# SLIM-PLO.net
KiCad netlist of a schematic drawn in EAGLE
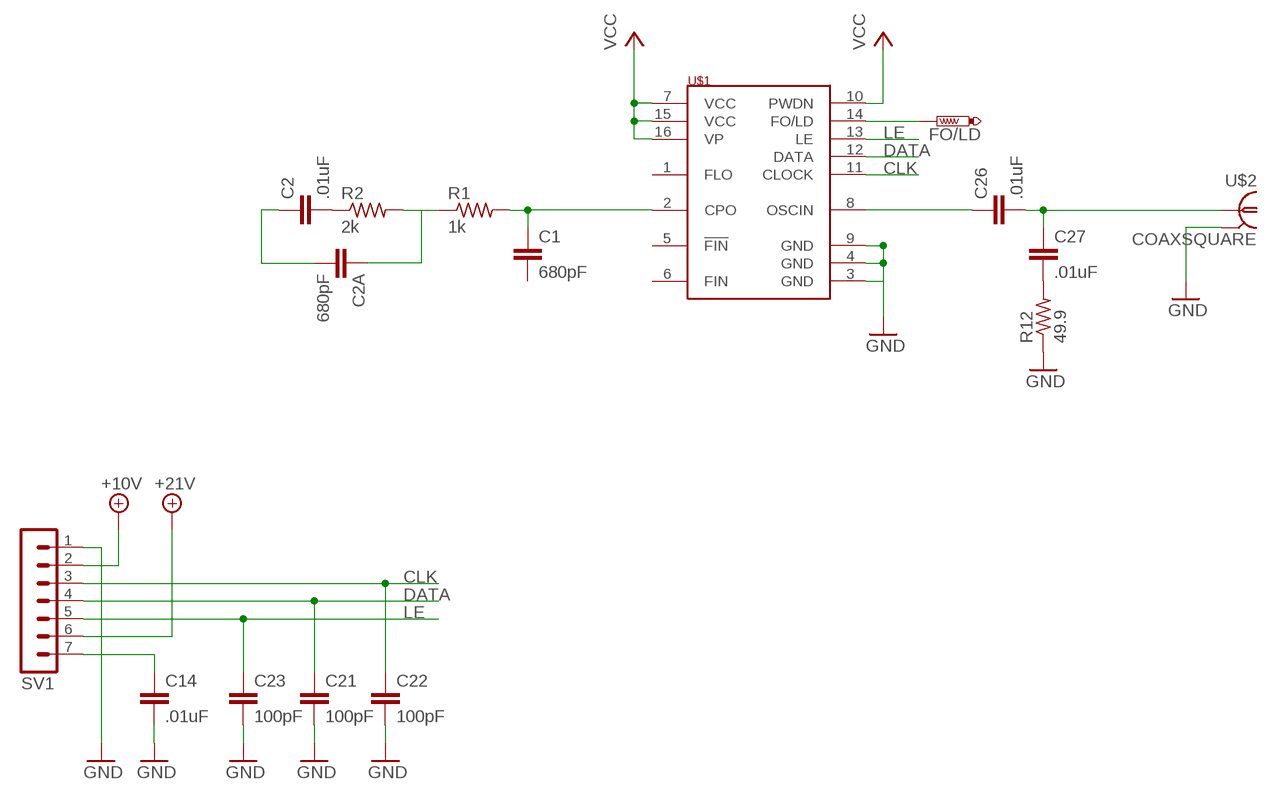
[diagram p0: schematic, sheet 1]

(export (version "E")
  (design (tool "Eeschema 10.0.6"))
  (components
    (comp (ref "C1")
      (value "680pF")
      (footprint "eagle-import:C0805")
      (libsource (lib "eagle-import") (part "C-EUC0805"))
    )
    (comp (ref "C2")
      (value ".01uF")
      (footprint "eagle-import:C0805")
      (libsource (lib "eagle-import") (part "C-EUC0805"))
    )
    (comp (ref "C2A")
      (value "680pF")
      (footprint "eagle-import:C0805")
      (libsource (lib "eagle-import") (part "C-EUC0805"))
    )
    (comp (ref "C14")
      (value ".01uF")
      (footprint "eagle-import:C0805")
      (libsource (lib "eagle-import") (part "C-EUC0805"))
    )
    (comp (ref "C21")
      (value "100pF")
      (footprint "eagle-import:C0805")
      (libsource (lib "eagle-import") (part "C-EUC0805"))
    )
    (comp (ref "C22")
      (value "100pF")
      (footprint "eagle-import:C0805")
      (libsource (lib "eagle-import") (part "C-EUC0805"))
    )
    (comp (ref "C23")
      (value "100pF")
      (footprint "eagle-import:C0805")
      (libsource (lib "eagle-import") (part "C-EUC0805"))
    )
    (comp (ref "C26")
      (value ".01uF")
      (footprint "eagle-import:C0805")
      (libsource (lib "eagle-import") (part "C-EUC0805"))
    )
    (comp (ref "C27")
      (value ".01uF")
      (footprint "eagle-import:C0805")
      (libsource (lib "eagle-import") (part "C-EUC0805"))
    )
    (comp (ref "FO/LD")
      (value "PTR1B1,27")
      (footprint "eagle-import:B1,27")
      (libsource (lib "eagle-import") (part "PTR1B1,27"))
    )
    (comp (ref "R1")
      (value "1k")
      (footprint "eagle-import:M0805")
      (libsource (lib "eagle-import") (part "R-US_M0805"))
    )
    (comp (ref "R2")
      (value "2k")
      (footprint "eagle-import:M0805")
      (libsource (lib "eagle-import") (part "R-US_M0805"))
    )
    (comp (ref "R12")
      (value "49.9")
      (footprint "eagle-import:M0805")
      (libsource (lib "eagle-import") (part "R-US_M0805"))
    )
    (comp (ref "SV1")
      (value "MA07-1")
      (footprint "eagle-import:MA07-1")
      (libsource (lib "eagle-import") (part "MA07-1"))
    )
    (comp (ref "U$1")
      (value "LMX2326")
      (footprint "eagle-import:TSSOP16")
      (libsource (lib "eagle-import") (part "LMX2326"))
    )
    (comp (ref "U$2")
      (value "COAXSQUARE")
      (footprint "eagle-import:SLIM_COAX_PAD")
      (libsource (lib "eagle-import") (part "COAX"))
    )
  )
  (nets
    (net (code "1") (name "+10V") (class "Default")
      (node (ref "SV1") (pin "2") (pinfunction "2_2") (pintype "passive"))
    )
    (net (code "2") (name "+21V") (class "Default")
      (node (ref "SV1") (pin "6") (pinfunction "6_6") (pintype "passive"))
    )
    (net (code "3") (name "/CLK") (class "Default")
      (node (ref "C22") (pin "1") (pinfunction "1_1") (pintype "passive"))
      (node (ref "SV1") (pin "3") (pinfunction "3_3") (pintype "passive"))
      (node (ref "U$1") (pin "11") (pinfunction "CLOCK_11") (pintype "bidirectional"))
    )
    (net (code "4") (name "/DATA") (class "Default")
      (node (ref "C21") (pin "1") (pinfunction "1_1") (pintype "passive"))
      (node (ref "SV1") (pin "4") (pinfunction "4_4") (pintype "passive"))
      (node (ref "U$1") (pin "12") (pinfunction "DATA_12") (pintype "bidirectional"))
    )
    (net (code "5") (name "/LE") (class "Default")
      (node (ref "C23") (pin "1") (pinfunction "1_1") (pintype "passive"))
      (node (ref "SV1") (pin "5") (pinfunction "5_5") (pintype "passive"))
      (node (ref "U$1") (pin "13") (pinfunction "LE_13") (pintype "bidirectional"))
    )
    (net (code "6") (name "GND") (class "Default")
      (node (ref "C14") (pin "2") (pinfunction "2_2") (pintype "passive"))
      (node (ref "C21") (pin "2") (pinfunction "2_2") (pintype "passive"))
      (node (ref "C22") (pin "2") (pinfunction "2_2") (pintype "passive"))
      (node (ref "C23") (pin "2") (pinfunction "2_2") (pintype "passive"))
      (node (ref "R12") (pin "1") (pinfunction "1_1") (pintype "passive"))
      (node (ref "SV1") (pin "1") (pinfunction "1_1") (pintype "passive"))
      (node (ref "U$1") (pin "3") (pinfunction "GND_3") (pintype "bidirectional"))
      (node (ref "U$1") (pin "4") (pinfunction "GND_4") (pintype "bidirectional"))
      (node (ref "U$1") (pin "9") (pinfunction "GND_9") (pintype "bidirectional"))
      (node (ref "U$2") (pin "P$2") (pinfunction "GND_P$2") (pintype "power_in"))
    )
    (net (code "7") (name "Net-(C2-Pad1)") (class "Default")
      (node (ref "C2") (pin "1") (pinfunction "1_1") (pintype "passive"))
      (node (ref "C2A") (pin "2") (pinfunction "2_2") (pintype "passive"))
    )
    (net (code "8") (name "Net-(C2-Pad2)") (class "Default")
      (node (ref "C2") (pin "2") (pinfunction "2_2") (pintype "passive"))
      (node (ref "R2") (pin "1") (pinfunction "1_1") (pintype "passive"))
    )
    (net (code "9") (name "Net-(C2A-Pad1)") (class "Default")
      (node (ref "C2A") (pin "1") (pinfunction "1_1") (pintype "passive"))
      (node (ref "R1") (pin "1") (pinfunction "1_1") (pintype "passive"))
      (node (ref "R2") (pin "2") (pinfunction "2_2") (pintype "passive"))
    )
    (net (code "10") (name "Net-(C14-Pad1)") (class "Default")
      (node (ref "C14") (pin "1") (pinfunction "1_1") (pintype "passive"))
      (node (ref "SV1") (pin "7") (pinfunction "7_7") (pintype "passive"))
    )
    (net (code "11") (name "Net-(C27-Pad2)") (class "Default")
      (node (ref "C27") (pin "2") (pinfunction "2_2") (pintype "passive"))
      (node (ref "R12") (pin "2") (pinfunction "2_2") (pintype "passive"))
    )
    (net (code "12") (name "Net-(U$1-CPO)") (class "Default")
      (node (ref "C1") (pin "1") (pinfunction "1_1") (pintype "passive"))
      (node (ref "R1") (pin "2") (pinfunction "2_2") (pintype "passive"))
      (node (ref "U$1") (pin "2") (pinfunction "CPO_2") (pintype "bidirectional"))
    )
    (net (code "13") (name "Net-(U$1-FO{slash}LD)") (class "Default")
      (node (ref "FO/LD") (pin "TP") (pinfunction "TP_TP") (pintype "input"))
      (node (ref "U$1") (pin "14") (pinfunction "FO/LD_14") (pintype "bidirectional"))
    )
    (net (code "14") (name "Net-(U$1-OSCIN)") (class "Default")
      (node (ref "C26") (pin "1") (pinfunction "1_1") (pintype "passive"))
      (node (ref "U$1") (pin "8") (pinfunction "OSCIN_8") (pintype "bidirectional"))
    )
    (net (code "15") (name "Net-(U$2-1)") (class "Default")
      (node (ref "C26") (pin "2") (pinfunction "2_2") (pintype "passive"))
      (node (ref "C27") (pin "1") (pinfunction "1_1") (pintype "passive"))
      (node (ref "U$2") (pin "P$1") (pinfunction "1_P$1") (pintype "passive"))
    )
    (net (code "16") (name "VCC") (class "Default")
      (node (ref "U$1") (pin "10") (pinfunction "PWDN_10") (pintype "bidirectional"))
      (node (ref "U$1") (pin "15") (pinfunction "VCC_15") (pintype "bidirectional"))
      (node (ref "U$1") (pin "16") (pinfunction "VP_16") (pintype "bidirectional"))
      (node (ref "U$1") (pin "7") (pinfunction "VCC_7") (pintype "bidirectional"))
    )
    (net (code "17") (name "unconnected-(C1-Pad2)") (class "Default")
      (node (ref "C1") (pin "2") (pinfunction "2_2") (pintype "passive"))
    )
    (net (code "18") (name "unconnected-(U$1-FIN-Pad6)") (class "Default")
      (node (ref "U$1") (pin "6") (pinfunction "FIN_6") (pintype "bidirectional"))
    )
    (net (code "19") (name "unconnected-(U$1-FLO-Pad1)") (class "Default")
      (node (ref "U$1") (pin "1") (pinfunction "FLO_1") (pintype "bidirectional"))
    )
    (net (code "20") (name "unconnected-(U$1-~{FIN}-Pad5)") (class "Default")
      (node (ref "U$1") (pin "5") (pinfunction "~{FIN}_5") (pintype "bidirectional"))
    )
  )
)
